# Connectors.net
KiCad netlist of a schematic drawn in Altium Designer
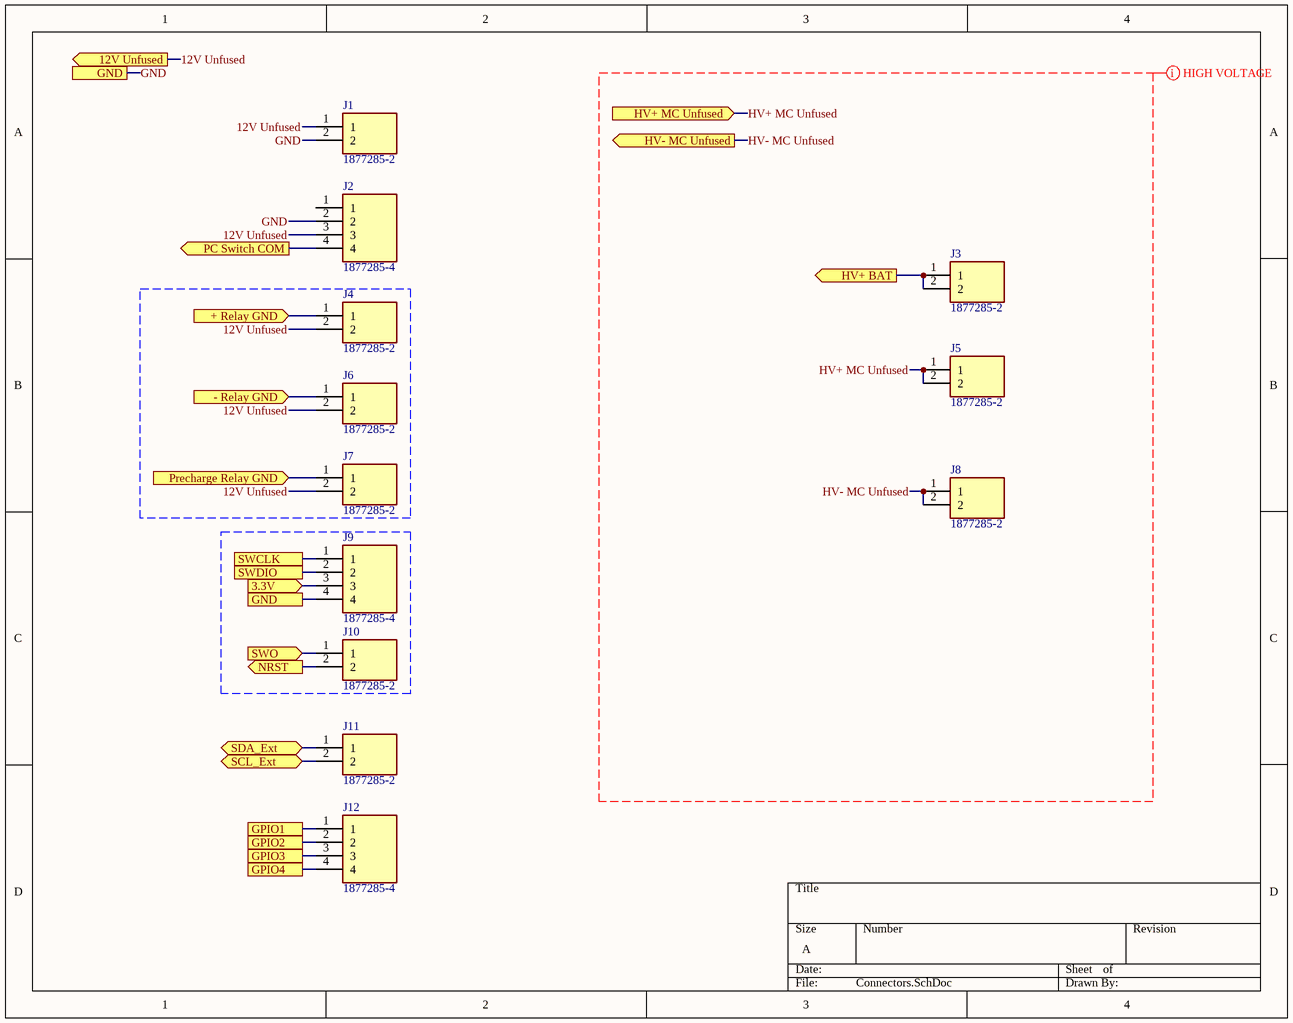
[diagram p0: Connectors.SchDoc]

(export (version "E")
  (design (tool "Eeschema 10.0.6"))
  (components
    (comp (ref "J1")
      (value "1877285-2")
      (footprint "SamacSys:18772852")
      (description "Connector")
      (fields (field (name "MOUSER PART NUMBER") "571-1877285-2"))
      (libsource (lib "SamacSys") (part "1877285-2"))
    )
    (comp (ref "J2")
      (value "1877285-4")
      (footprint "SamacSys:18772854")
      (description "Connector")
      (fields (field (name "MOUSER PART NUMBER") "571-1877285-4"))
      (libsource (lib "SamacSys") (part "1877285-4"))
    )
    (comp (ref "J3")
      (value "1877285-2")
      (footprint "SamacSys:18772852")
      (description "Connector")
      (fields (field (name "MOUSER PART NUMBER") "571-1877285-2"))
      (libsource (lib "SamacSys") (part "1877285-2"))
    )
    (comp (ref "J4")
      (value "1877285-2")
      (footprint "SamacSys:18772852")
      (description "Connector")
      (fields (field (name "MOUSER PART NUMBER") "571-1877285-2"))
      (libsource (lib "SamacSys") (part "1877285-2"))
    )
    (comp (ref "J5")
      (value "1877285-2")
      (footprint "SamacSys:18772852")
      (description "Connector")
      (fields (field (name "MOUSER PART NUMBER") "571-1877285-2"))
      (libsource (lib "SamacSys") (part "1877285-2"))
    )
    (comp (ref "J6")
      (value "1877285-2")
      (footprint "SamacSys:18772852")
      (description "Connector")
      (fields (field (name "MOUSER PART NUMBER") "571-1877285-2"))
      (libsource (lib "SamacSys") (part "1877285-2"))
    )
    (comp (ref "J7")
      (value "1877285-2")
      (footprint "SamacSys:18772852")
      (description "Connector")
      (fields (field (name "MOUSER PART NUMBER") "571-1877285-2"))
      (libsource (lib "SamacSys") (part "1877285-2"))
    )
    (comp (ref "J8")
      (value "1877285-2")
      (footprint "SamacSys:18772852")
      (description "Connector")
      (fields (field (name "MOUSER PART NUMBER") "571-1877285-2"))
      (libsource (lib "SamacSys") (part "1877285-2"))
    )
    (comp (ref "J9")
      (value "1877285-4")
      (footprint "SamacSys:18772854")
      (description "Connector")
      (fields (field (name "MOUSER PART NUMBER") "571-1877285-4"))
      (libsource (lib "SamacSys") (part "1877285-4"))
    )
    (comp (ref "J10")
      (value "1877285-2")
      (footprint "SamacSys:18772852")
      (description "Connector")
      (fields (field (name "MOUSER PART NUMBER") "571-1877285-2"))
      (libsource (lib "SamacSys") (part "1877285-2"))
    )
    (comp (ref "J11")
      (value "1877285-2")
      (footprint "SamacSys:18772852")
      (description "Connector")
      (fields (field (name "MOUSER PART NUMBER") "571-1877285-2"))
      (libsource (lib "SamacSys") (part "1877285-2"))
    )
    (comp (ref "J12")
      (value "1877285-4")
      (footprint "SamacSys:18772854")
      (description "Connector")
      (fields (field (name "MOUSER PART NUMBER") "571-1877285-4"))
      (libsource (lib "SamacSys") (part "1877285-4"))
    )
  )
  (nets
    (net (code "1") (name "/+ Relay GND") (class "Default")
      (node (ref "J4") (pin "1") (pinfunction "1_1") (pintype "passive"))
    )
    (net (code "2") (name "/- Relay GND") (class "Default")
      (node (ref "J6") (pin "1") (pinfunction "1_1") (pintype "passive"))
    )
    (net (code "3") (name "/3.3V") (class "Default")
      (node (ref "J9") (pin "3") (pinfunction "3_3") (pintype "passive"))
    )
    (net (code "4") (name "/12V Unfused") (class "Default")
      (node (ref "J1") (pin "1") (pinfunction "1_1") (pintype "passive"))
      (node (ref "J2") (pin "3") (pinfunction "3_3") (pintype "passive"))
      (node (ref "J4") (pin "2") (pinfunction "2_2") (pintype "passive"))
      (node (ref "J6") (pin "2") (pinfunction "2_2") (pintype "passive"))
      (node (ref "J7") (pin "2") (pinfunction "2_2") (pintype "passive"))
    )
    (net (code "5") (name "/GND") (class "Default")
      (node (ref "J1") (pin "2") (pinfunction "2_2") (pintype "passive"))
      (node (ref "J2") (pin "2") (pinfunction "2_2") (pintype "passive"))
      (node (ref "J9") (pin "4") (pinfunction "4_4") (pintype "passive"))
    )
    (net (code "6") (name "/GPIO1") (class "Default")
      (node (ref "J12") (pin "1") (pinfunction "1_1") (pintype "passive"))
    )
    (net (code "7") (name "/GPIO2") (class "Default")
      (node (ref "J12") (pin "2") (pinfunction "2_2") (pintype "passive"))
    )
    (net (code "8") (name "/GPIO3") (class "Default")
      (node (ref "J12") (pin "3") (pinfunction "3_3") (pintype "passive"))
    )
    (net (code "9") (name "/GPIO4") (class "Default")
      (node (ref "J12") (pin "4") (pinfunction "4_4") (pintype "passive"))
    )
    (net (code "10") (name "/HV+ BAT") (class "Default")
      (node (ref "J3") (pin "1") (pinfunction "1_1") (pintype "passive"))
      (node (ref "J3") (pin "2") (pinfunction "2_2") (pintype "passive"))
    )
    (net (code "11") (name "/HV+ MC Unfused") (class "Default")
      (node (ref "J5") (pin "1") (pinfunction "1_1") (pintype "passive"))
      (node (ref "J5") (pin "2") (pinfunction "2_2") (pintype "passive"))
    )
    (net (code "12") (name "/HV- MC Unfused") (class "Default")
      (node (ref "J8") (pin "1") (pinfunction "1_1") (pintype "passive"))
      (node (ref "J8") (pin "2") (pinfunction "2_2") (pintype "passive"))
    )
    (net (code "13") (name "/NRST") (class "Default")
      (node (ref "J10") (pin "2") (pinfunction "2_2") (pintype "passive"))
    )
    (net (code "14") (name "/PC Switch COM") (class "Default")
      (node (ref "J2") (pin "4") (pinfunction "4_4") (pintype "passive"))
    )
    (net (code "15") (name "/Precharge Relay GND") (class "Default")
      (node (ref "J7") (pin "1") (pinfunction "1_1") (pintype "passive"))
    )
    (net (code "16") (name "/SCL_Ext") (class "Default")
      (node (ref "J11") (pin "2") (pinfunction "2_2") (pintype "passive"))
    )
    (net (code "17") (name "/SDA_Ext") (class "Default")
      (node (ref "J11") (pin "1") (pinfunction "1_1") (pintype "passive"))
    )
    (net (code "18") (name "/SWCLK") (class "Default")
      (node (ref "J9") (pin "1") (pinfunction "1_1") (pintype "passive"))
    )
    (net (code "19") (name "/SWDIO") (class "Default")
      (node (ref "J9") (pin "2") (pinfunction "2_2") (pintype "passive"))
    )
    (net (code "20") (name "/SWO") (class "Default")
      (node (ref "J10") (pin "1") (pinfunction "1_1") (pintype "passive"))
    )
    (net (code "21") (name "unconnected-(J2-Pad1)") (class "Default")
      (node (ref "J2") (pin "1") (pinfunction "1_1") (pintype "passive"))
    )
  )
)
